# source_eagle.net
KiCad netlist of a schematic drawn in EAGLE
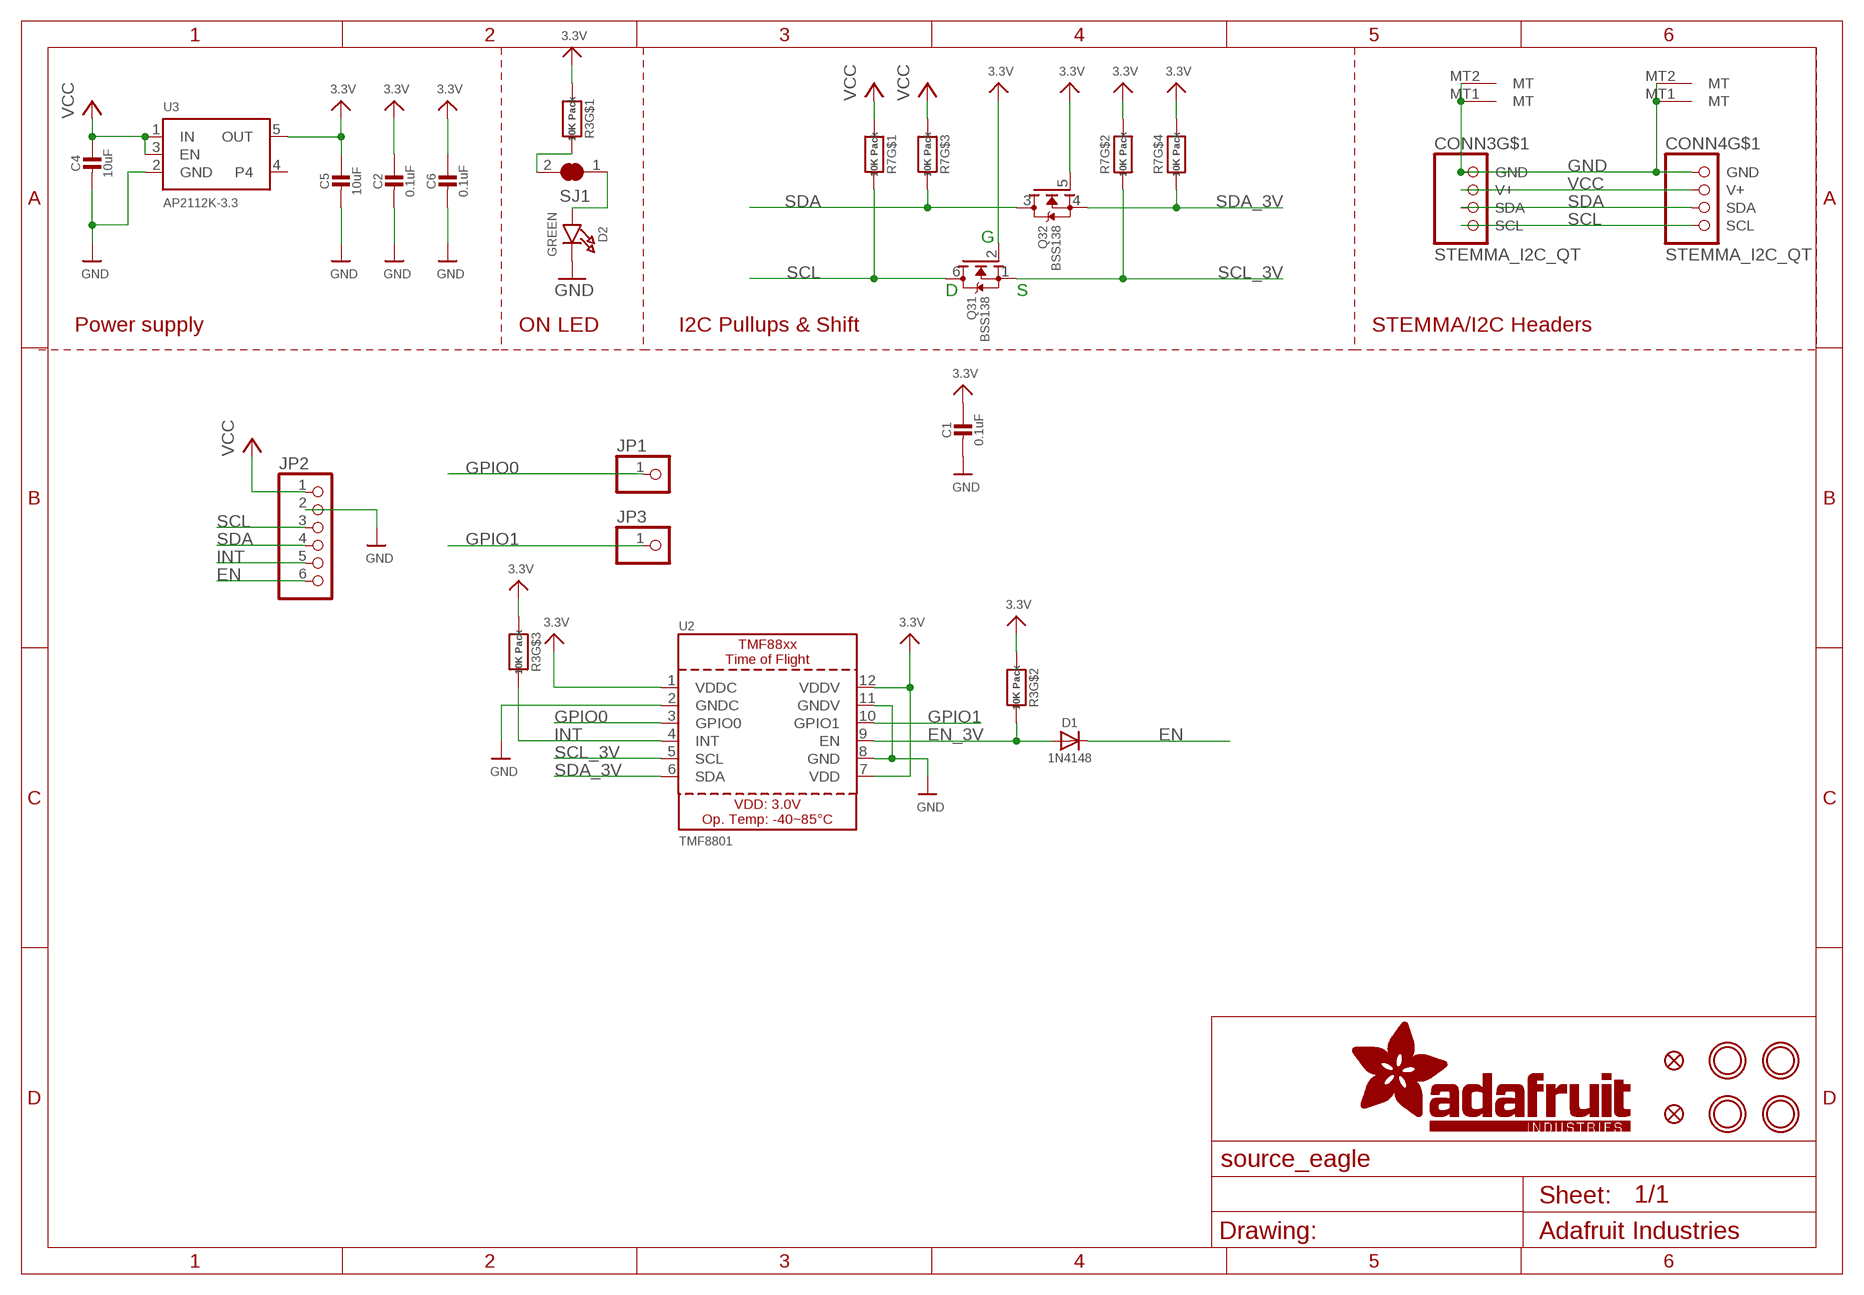
[diagram p0: schematic, sheet 1]

(export (version "E")
  (design (tool "Eeschema 10.0.6"))
  (components
    (comp (ref "C1")
      (value "0.1uF")
      (footprint "eagle-import:0603-NO")
      (libsource (lib "eagle-import") (part "CAP_CERAMIC0603_NO"))
    )
    (comp (ref "C2")
      (value "0.1uF")
      (footprint "eagle-import:0603-NO")
      (libsource (lib "eagle-import") (part "CAP_CERAMIC0603_NO"))
    )
    (comp (ref "C4")
      (value "10uF")
      (footprint "eagle-import:0805-NO")
      (libsource (lib "eagle-import") (part "CAP_CERAMIC0805-NOOUTLINE"))
    )
    (comp (ref "C5")
      (value "10uF")
      (footprint "eagle-import:0805-NO")
      (libsource (lib "eagle-import") (part "CAP_CERAMIC0805-NOOUTLINE"))
    )
    (comp (ref "C6")
      (value "0.1uF")
      (footprint "eagle-import:0603-NO")
      (libsource (lib "eagle-import") (part "CAP_CERAMIC0603_NO"))
    )
    (comp (ref "CONN3")
      (value "STEMMA_I2C_QT")
      (footprint "eagle-import:JST_SH4")
      (libsource (lib "eagle-import") (part "STEMMA_I2C_QT"))
    )
    (comp (ref "CONN4")
      (value "STEMMA_I2C_QT")
      (footprint "eagle-import:JST_SH4")
      (libsource (lib "eagle-import") (part "STEMMA_I2C_QT"))
    )
    (comp (ref "D1")
      (value "1N4148")
      (footprint "eagle-import:SOD-323")
      (libsource (lib "eagle-import") (part "DIODESOD-323"))
    )
    (comp (ref "D2")
      (value "GREEN")
      (footprint "eagle-import:CHIPLED_0603_NOOUTLINE")
      (libsource (lib "eagle-import") (part "LED0603_NOOUTLINE"))
    )
    (comp (ref "FID1")
      (value "FIDUCIAL_0.5MM")
      (footprint "eagle-import:FIDUCIAL_0.5MM")
      (libsource (lib "eagle-import") (part "FIDUCIAL_0.5MM"))
    )
    (comp (ref "FID4")
      (value "FIDUCIAL_0.5MM")
      (footprint "eagle-import:FIDUCIAL_0.5MM")
      (libsource (lib "eagle-import") (part "FIDUCIAL_0.5MM"))
    )
    (comp (ref "JP1")
      (value "HEADER-1X1ROUND")
      (footprint "eagle-import:1X01_ROUND")
      (libsource (lib "eagle-import") (part "HEADER-1X1ROUND"))
    )
    (comp (ref "JP2")
      (value "HEADER-1X670MIL")
      (footprint "eagle-import:1X06_ROUND_70")
      (libsource (lib "eagle-import") (part "HEADER-1X670MIL"))
    )
    (comp (ref "JP3")
      (value "HEADER-1X1ROUND")
      (footprint "eagle-import:1X01_ROUND")
      (libsource (lib "eagle-import") (part "HEADER-1X1ROUND"))
    )
    (comp (ref "Q3")
      (value "BSS138")
      (footprint "eagle-import:SOT363")
      (libsource (lib "eagle-import") (part "MOSFET-N_DUAL"))
    )
    (comp (ref "R3")
      (value "10K Pack")
      (footprint "eagle-import:RESPACK_4X0603")
      (libsource (lib "eagle-import") (part "RESISTOR_4PACK"))
    )
    (comp (ref "R7")
      (value "10K Pack")
      (footprint "eagle-import:RESPACK_4X0603")
      (libsource (lib "eagle-import") (part "RESISTOR_4PACK"))
    )
    (comp (ref "SJ1")
      (value "SOLDERJUMPER_CLOSED")
      (footprint "eagle-import:SOLDERJUMPER_CLOSEDWIRE")
      (libsource (lib "eagle-import") (part "SOLDERJUMPER_CLOSED"))
    )
    (comp (ref "U$30")
      (value "MOUNTINGHOLE2.5")
      (footprint "eagle-import:MOUNTINGHOLE_2.5_PLATED")
      (libsource (lib "eagle-import") (part "MOUNTINGHOLE2.5"))
    )
    (comp (ref "U$31")
      (value "MOUNTINGHOLE2.5")
      (footprint "eagle-import:MOUNTINGHOLE_2.5_PLATED")
      (libsource (lib "eagle-import") (part "MOUNTINGHOLE2.5"))
    )
    (comp (ref "U$33")
      (value "MOUNTINGHOLE2.5")
      (footprint "eagle-import:MOUNTINGHOLE_2.5_PLATED")
      (libsource (lib "eagle-import") (part "MOUNTINGHOLE2.5"))
    )
    (comp (ref "U$34")
      (value "MOUNTINGHOLE2.5")
      (footprint "eagle-import:MOUNTINGHOLE_2.5_PLATED")
      (libsource (lib "eagle-import") (part "MOUNTINGHOLE2.5"))
    )
    (comp (ref "U2")
      (value "TMF8801")
      (footprint "eagle-import:TMF880X")
      (libsource (lib "eagle-import") (part "TMF880X_12"))
    )
    (comp (ref "U3")
      (value "AP2112K-3.3")
      (footprint "eagle-import:SOT23-5")
      (fields (field (name "JLC_ROTATION") "0"))
      (libsource (lib "eagle-import") (part "VREG_SOT23-5"))
    )
  )
  (nets
    (net (code "1") (name "/EN") (class "Default")
      (node (ref "D1") (pin "C") (pinfunction "C_C") (pintype "passive"))
      (node (ref "JP2") (pin "6") (pinfunction "6_6") (pintype "passive"))
    )
    (net (code "2") (name "/EN_3V") (class "Default")
      (node (ref "D1") (pin "A") (pinfunction "A_A") (pintype "passive"))
      (node (ref "R3") (pin "7") (pinfunction "2_7") (pintype "passive"))
      (node (ref "U2") (pin "9") (pinfunction "EN_9") (pintype "bidirectional"))
    )
    (net (code "3") (name "/GPIO0") (class "Default")
      (node (ref "JP1") (pin "1") (pinfunction "1_1") (pintype "passive"))
      (node (ref "U2") (pin "3") (pinfunction "GPIO0_3") (pintype "bidirectional"))
    )
    (net (code "4") (name "/GPIO1") (class "Default")
      (node (ref "JP3") (pin "1") (pinfunction "1_1") (pintype "passive"))
      (node (ref "U2") (pin "10") (pinfunction "GPIO1_10") (pintype "bidirectional"))
    )
    (net (code "5") (name "/INT") (class "Default")
      (node (ref "JP2") (pin "5") (pinfunction "5_5") (pintype "passive"))
      (node (ref "R3") (pin "6") (pinfunction "2_6") (pintype "passive"))
      (node (ref "U2") (pin "4") (pinfunction "INT_4") (pintype "bidirectional"))
    )
    (net (code "6") (name "/SCL") (class "Default")
      (node (ref "CONN3") (pin "4") (pinfunction "SCL_4") (pintype "passive"))
      (node (ref "CONN4") (pin "4") (pinfunction "SCL_4") (pintype "passive"))
      (node (ref "JP2") (pin "3") (pinfunction "3_3") (pintype "passive"))
      (node (ref "Q3") (pin "6") (pinfunction "D_6") (pintype "bidirectional"))
      (node (ref "R7") (pin "8") (pinfunction "2_8") (pintype "passive"))
    )
    (net (code "7") (name "/SCL_3V") (class "Default")
      (node (ref "Q3") (pin "1") (pinfunction "S_1") (pintype "bidirectional"))
      (node (ref "R7") (pin "7") (pinfunction "2_7") (pintype "passive"))
      (node (ref "U2") (pin "5") (pinfunction "SCL_5") (pintype "input"))
    )
    (net (code "8") (name "/SDA") (class "Default")
      (node (ref "CONN3") (pin "3") (pinfunction "SDA_3") (pintype "passive"))
      (node (ref "CONN4") (pin "3") (pinfunction "SDA_3") (pintype "passive"))
      (node (ref "JP2") (pin "4") (pinfunction "4_4") (pintype "passive"))
      (node (ref "Q3") (pin "3") (pinfunction "D_3") (pintype "bidirectional"))
      (node (ref "R7") (pin "6") (pinfunction "2_6") (pintype "passive"))
    )
    (net (code "9") (name "/SDA_3V") (class "Default")
      (node (ref "Q3") (pin "4") (pinfunction "S_4") (pintype "bidirectional"))
      (node (ref "R7") (pin "5") (pinfunction "2_5") (pintype "passive"))
      (node (ref "U2") (pin "6") (pinfunction "SDA_6") (pintype "bidirectional"))
    )
    (net (code "10") (name "3.3V") (class "Default")
      (node (ref "C1") (pin "1") (pinfunction "1_1") (pintype "passive"))
      (node (ref "C2") (pin "1") (pinfunction "1_1") (pintype "passive"))
      (node (ref "C5") (pin "1") (pinfunction "1_1") (pintype "passive"))
      (node (ref "C6") (pin "1") (pinfunction "1_1") (pintype "passive"))
      (node (ref "Q3") (pin "2") (pinfunction "G_2") (pintype "bidirectional"))
      (node (ref "Q3") (pin "5") (pinfunction "G_5") (pintype "bidirectional"))
      (node (ref "R3") (pin "1") (pinfunction "1_1") (pintype "passive"))
      (node (ref "R3") (pin "2") (pinfunction "1_2") (pintype "passive"))
      (node (ref "R3") (pin "3") (pinfunction "1_3") (pintype "passive"))
      (node (ref "R7") (pin "2") (pinfunction "1_2") (pintype "passive"))
      (node (ref "R7") (pin "4") (pinfunction "1_4") (pintype "passive"))
      (node (ref "U2") (pin "1") (pinfunction "VDDC_1") (pintype "power_in"))
      (node (ref "U2") (pin "12") (pinfunction "VDDV_12") (pintype "power_in"))
      (node (ref "U2") (pin "7") (pinfunction "VDD_7") (pintype "power_in"))
      (node (ref "U3") (pin "5") (pinfunction "OUT_5") (pintype "power_in"))
    )
    (net (code "11") (name "GND") (class "Default")
      (node (ref "C1") (pin "2") (pinfunction "2_2") (pintype "passive"))
      (node (ref "C2") (pin "2") (pinfunction "2_2") (pintype "passive"))
      (node (ref "C4") (pin "2") (pinfunction "2_2") (pintype "passive"))
      (node (ref "C5") (pin "2") (pinfunction "2_2") (pintype "passive"))
      (node (ref "C6") (pin "2") (pinfunction "2_2") (pintype "passive"))
      (node (ref "CONN3") (pin "1") (pinfunction "GND_1") (pintype "passive"))
      (node (ref "CONN3") (pin "MT1") (pinfunction "MT_MT1") (pintype "bidirectional"))
      (node (ref "CONN3") (pin "MT2") (pinfunction "MT_MT2") (pintype "bidirectional"))
      (node (ref "CONN4") (pin "1") (pinfunction "GND_1") (pintype "passive"))
      (node (ref "CONN4") (pin "MT1") (pinfunction "MT_MT1") (pintype "bidirectional"))
      (node (ref "CONN4") (pin "MT2") (pinfunction "MT_MT2") (pintype "bidirectional"))
      (node (ref "D2") (pin "C") (pinfunction "C_C") (pintype "passive"))
      (node (ref "JP2") (pin "2") (pinfunction "2_2") (pintype "passive"))
      (node (ref "U2") (pin "11") (pinfunction "GNDV_11") (pintype "power_in"))
      (node (ref "U2") (pin "2") (pinfunction "GNDC_2") (pintype "power_in"))
      (node (ref "U2") (pin "8") (pinfunction "GND_8") (pintype "power_in"))
      (node (ref "U3") (pin "2") (pinfunction "GND_2") (pintype "power_in"))
    )
    (net (code "12") (name "Net-(D2-PadA)") (class "Default")
      (node (ref "D2") (pin "A") (pinfunction "A_A") (pintype "passive"))
      (node (ref "SJ1") (pin "1") (pinfunction "1_1") (pintype "passive"))
    )
    (net (code "13") (name "Net-(R3A-2)") (class "Default")
      (node (ref "R3") (pin "8") (pinfunction "2_8") (pintype "passive"))
      (node (ref "SJ1") (pin "2") (pinfunction "2_2") (pintype "passive"))
    )
    (net (code "14") (name "VCC") (class "Default")
      (node (ref "C4") (pin "1") (pinfunction "1_1") (pintype "passive"))
      (node (ref "CONN3") (pin "2") (pinfunction "V+_2") (pintype "passive"))
      (node (ref "CONN4") (pin "2") (pinfunction "V+_2") (pintype "passive"))
      (node (ref "JP2") (pin "1") (pinfunction "1_1") (pintype "passive"))
      (node (ref "R7") (pin "1") (pinfunction "1_1") (pintype "passive"))
      (node (ref "R7") (pin "3") (pinfunction "1_3") (pintype "passive"))
      (node (ref "U3") (pin "1") (pinfunction "IN_1") (pintype "power_in"))
      (node (ref "U3") (pin "3") (pinfunction "EN_3") (pintype "input"))
    )
    (net (code "15") (name "unconnected-(U3-P4-Pad4)") (class "Default")
      (node (ref "U3") (pin "4") (pinfunction "P4_4") (pintype "bidirectional"))
    )
  )
)
